# followLineMain.net
KiCad netlist of a schematic drawn in EAGLE
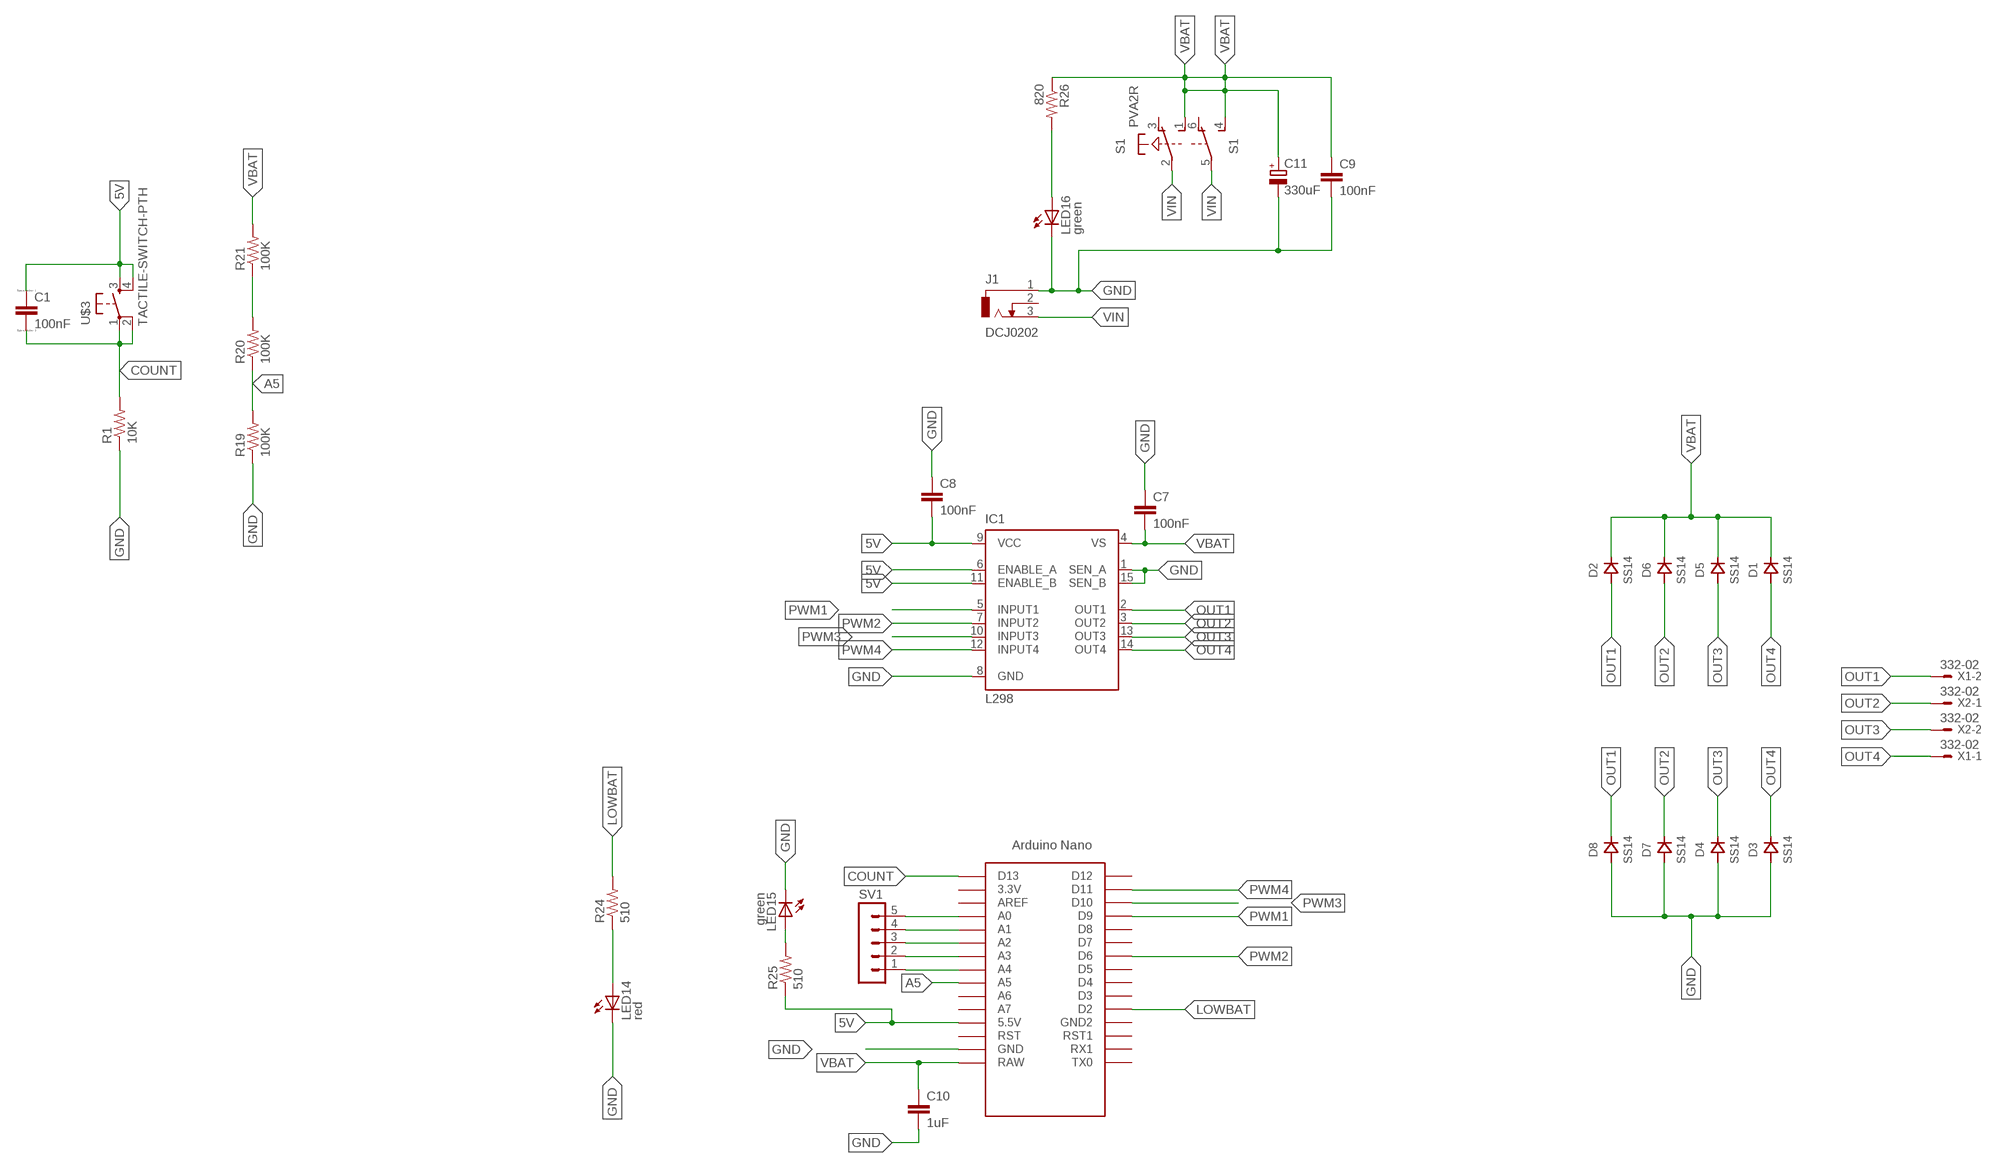
[diagram p0: schematic, sheet 1]

(export (version "E")
  (design (tool "Eeschema 10.0.6"))
  (components
    (comp (ref "C1")
      (value "100nF")
      (footprint "eagle-import:C0603")
      (libsource (lib "eagle-import") (part "CC0603"))
    )
    (comp (ref "C7")
      (value "100nF")
      (footprint "eagle-import:0805")
      (libsource (lib "eagle-import") (part "CAP0805"))
    )
    (comp (ref "C8")
      (value "100nF")
      (footprint "eagle-import:0805")
      (libsource (lib "eagle-import") (part "CAP0805"))
    )
    (comp (ref "C9")
      (value "100nF")
      (footprint "eagle-import:0805")
      (libsource (lib "eagle-import") (part "CAP0805"))
    )
    (comp (ref "C10")
      (value "1uF")
      (footprint "eagle-import:1206")
      (libsource (lib "eagle-import") (part "CAP1206"))
    )
    (comp (ref "C11")
      (value "330uF")
      (footprint "eagle-import:E5-13")
      (libsource (lib "eagle-import") (part "CPOL-EUE5-13"))
    )
    (comp (ref "D1")
      (value "SS14")
      (footprint "eagle-import:DO214")
      (libsource (lib "eagle-import") (part "SS14"))
    )
    (comp (ref "D2")
      (value "SS14")
      (footprint "eagle-import:DO214")
      (libsource (lib "eagle-import") (part "SS14"))
    )
    (comp (ref "D3")
      (value "SS14")
      (footprint "eagle-import:DO214")
      (libsource (lib "eagle-import") (part "SS14"))
    )
    (comp (ref "D4")
      (value "SS14")
      (footprint "eagle-import:DO214")
      (libsource (lib "eagle-import") (part "SS14"))
    )
    (comp (ref "D5")
      (value "SS14")
      (footprint "eagle-import:DO214")
      (libsource (lib "eagle-import") (part "SS14"))
    )
    (comp (ref "D6")
      (value "SS14")
      (footprint "eagle-import:DO214")
      (libsource (lib "eagle-import") (part "SS14"))
    )
    (comp (ref "D7")
      (value "SS14")
      (footprint "eagle-import:DO214")
      (libsource (lib "eagle-import") (part "SS14"))
    )
    (comp (ref "D8")
      (value "SS14")
      (footprint "eagle-import:DO214")
      (libsource (lib "eagle-import") (part "SS14"))
    )
    (comp (ref "IC1")
      (value "L298")
      (footprint "eagle-import:MULTIWATT-15")
      (fields (field (name "MPN") "L298N"))
      (libsource (lib "eagle-import") (part "L298"))
    )
    (comp (ref "J1")
      (value "DCJ0202")
      (footprint "eagle-import:DCJ0202")
      (libsource (lib "eagle-import") (part "DCJ0202"))
    )
    (comp (ref "LED14")
      (value "red")
      (footprint "eagle-import:SML0805")
      (libsource (lib "eagle-import") (part "LEDSML0805"))
    )
    (comp (ref "LED15")
      (value "green")
      (footprint "eagle-import:SML0805")
      (libsource (lib "eagle-import") (part "LEDSML0805"))
    )
    (comp (ref "LED16")
      (value "green")
      (footprint "eagle-import:SML0805")
      (libsource (lib "eagle-import") (part "LEDSML0805"))
    )
    (comp (ref "R1")
      (value "10K")
      (footprint "eagle-import:0805")
      (libsource (lib "eagle-import") (part "RESISTOR0805-RES"))
    )
    (comp (ref "R19")
      (value "100K")
      (footprint "eagle-import:0805")
      (libsource (lib "eagle-import") (part "RESISTOR0805-RES"))
    )
    (comp (ref "R20")
      (value "100K")
      (footprint "eagle-import:0805")
      (libsource (lib "eagle-import") (part "RESISTOR0805-RES"))
    )
    (comp (ref "R21")
      (value "100K")
      (footprint "eagle-import:0805")
      (libsource (lib "eagle-import") (part "RESISTOR0805-RES"))
    )
    (comp (ref "R24")
      (value "510")
      (footprint "eagle-import:0805")
      (libsource (lib "eagle-import") (part "RESISTOR0805-RES"))
    )
    (comp (ref "R25")
      (value "510")
      (footprint "eagle-import:0805")
      (libsource (lib "eagle-import") (part "RESISTOR0805-RES"))
    )
    (comp (ref "R26")
      (value "820")
      (footprint "eagle-import:0805")
      (libsource (lib "eagle-import") (part "RESISTOR0805-RES"))
    )
    (comp (ref "S1")
      (value "PVA2R")
      (footprint "eagle-import:PVA2R")
      (libsource (lib "eagle-import") (part "PVA2R"))
    )
    (comp (ref "SV1")
      (value "MA05-1")
      (footprint "eagle-import:MA05-1")
      (libsource (lib "eagle-import") (part "MA05-1"))
    )
    (comp (ref "U$1")
      (value "NANO")
      (footprint "eagle-import:NANO")
      (libsource (lib "eagle-import") (part "NANO"))
    )
    (comp (ref "U$3")
      (value "TACTILE-SWITCH-PTH")
      (footprint "eagle-import:TAC-SWITCH-PTH")
      (libsource (lib "eagle-import") (part "TACTILE-SWITCH-PTH"))
    )
    (comp (ref "X1")
      (value "332-02")
      (footprint "eagle-import:332-02")
      (libsource (lib "eagle-import") (part "332-02"))
    )
    (comp (ref "X2")
      (value "332-02")
      (footprint "eagle-import:332-02")
      (libsource (lib "eagle-import") (part "332-02"))
    )
  )
  (nets
    (net (code "1") (name "5V") (class "Default")
      (node (ref "C1") (pin "1") (pinfunction "1_1") (pintype "passive"))
      (node (ref "C8") (pin "2") (pinfunction "2_2") (pintype "passive"))
      (node (ref "IC1") (pin "11") (pinfunction "ENABLE_B_11") (pintype "input"))
      (node (ref "IC1") (pin "6") (pinfunction "ENABLE_A_6") (pintype "input"))
      (node (ref "IC1") (pin "9") (pinfunction "VCC_9") (pintype "power_in"))
      (node (ref "R25") (pin "1") (pinfunction "1_1") (pintype "passive"))
      (node (ref "U$1") (pin "5V") (pinfunction "5.5V_5V") (pintype "bidirectional"))
      (node (ref "U$3") (pin "3") (pinfunction "3_3") (pintype "passive"))
      (node (ref "U$3") (pin "4") (pinfunction "4_4") (pintype "passive"))
    )
    (net (code "2") (name "A5") (class "Default")
      (node (ref "R19") (pin "2") (pinfunction "2_2") (pintype "passive"))
      (node (ref "R20") (pin "1") (pinfunction "1_1") (pintype "passive"))
      (node (ref "U$1") (pin "A5") (pinfunction "A5_A5") (pintype "bidirectional"))
    )
    (net (code "3") (name "COUNT") (class "Default")
      (node (ref "C1") (pin "2") (pinfunction "2_2") (pintype "passive"))
      (node (ref "R1") (pin "2") (pinfunction "2_2") (pintype "passive"))
      (node (ref "U$1") (pin "D13") (pinfunction "D13_D13") (pintype "bidirectional"))
      (node (ref "U$3") (pin "1") (pinfunction "1_1") (pintype "passive"))
      (node (ref "U$3") (pin "2") (pinfunction "2_2") (pintype "passive"))
    )
    (net (code "4") (name "GND") (class "Default")
      (node (ref "C10") (pin "2") (pinfunction "2_2") (pintype "passive"))
      (node (ref "C11") (pin "-") (pinfunction "-_-") (pintype "passive"))
      (node (ref "C7") (pin "1") (pinfunction "1_1") (pintype "passive"))
      (node (ref "C8") (pin "1") (pinfunction "1_1") (pintype "passive"))
      (node (ref "C9") (pin "2") (pinfunction "2_2") (pintype "passive"))
      (node (ref "D3") (pin "ANODE") (pinfunction "ANODE_ANODE") (pintype "bidirectional"))
      (node (ref "D4") (pin "ANODE") (pinfunction "ANODE_ANODE") (pintype "bidirectional"))
      (node (ref "D7") (pin "ANODE") (pinfunction "ANODE_ANODE") (pintype "bidirectional"))
      (node (ref "D8") (pin "ANODE") (pinfunction "ANODE_ANODE") (pintype "bidirectional"))
      (node (ref "IC1") (pin "1") (pinfunction "SEN_A_1") (pintype "input"))
      (node (ref "IC1") (pin "15") (pinfunction "SEN_B_15") (pintype "input"))
      (node (ref "IC1") (pin "8") (pinfunction "GND_8") (pintype "power_in"))
      (node (ref "J1") (pin "1") (pinfunction "1_1") (pintype "passive"))
      (node (ref "LED14") (pin "C") (pinfunction "C_C") (pintype "passive"))
      (node (ref "LED15") (pin "C") (pinfunction "C_C") (pintype "passive"))
      (node (ref "LED16") (pin "C") (pinfunction "C_C") (pintype "passive"))
      (node (ref "R1") (pin "1") (pinfunction "1_1") (pintype "passive"))
      (node (ref "R19") (pin "1") (pinfunction "1_1") (pintype "passive"))
      (node (ref "U$1") (pin "GND") (pinfunction "GND_GND") (pintype "bidirectional"))
    )
    (net (code "5") (name "LOWBAT") (class "Default")
      (node (ref "R24") (pin "2") (pinfunction "2_2") (pintype "passive"))
      (node (ref "U$1") (pin "D2") (pinfunction "D2_D2") (pintype "bidirectional"))
    )
    (net (code "6") (name "Net-(LED14-PadA)") (class "Default")
      (node (ref "LED14") (pin "A") (pinfunction "A_A") (pintype "passive"))
      (node (ref "R24") (pin "1") (pinfunction "1_1") (pintype "passive"))
    )
    (net (code "7") (name "Net-(LED15-PadA)") (class "Default")
      (node (ref "LED15") (pin "A") (pinfunction "A_A") (pintype "passive"))
      (node (ref "R25") (pin "2") (pinfunction "2_2") (pintype "passive"))
    )
    (net (code "8") (name "Net-(LED16-PadA)") (class "Default")
      (node (ref "LED16") (pin "A") (pinfunction "A_A") (pintype "passive"))
      (node (ref "R26") (pin "2") (pinfunction "2_2") (pintype "passive"))
    )
    (net (code "9") (name "Net-(R20-Pad2)") (class "Default")
      (node (ref "R20") (pin "2") (pinfunction "2_2") (pintype "passive"))
      (node (ref "R21") (pin "1") (pinfunction "1_1") (pintype "passive"))
    )
    (net (code "10") (name "Net-(SV1-Pad1)") (class "Default")
      (node (ref "SV1") (pin "1") (pinfunction "1_1") (pintype "passive"))
      (node (ref "U$1") (pin "A4") (pinfunction "A4_A4") (pintype "bidirectional"))
    )
    (net (code "11") (name "Net-(SV1-Pad2)") (class "Default")
      (node (ref "SV1") (pin "2") (pinfunction "2_2") (pintype "passive"))
      (node (ref "U$1") (pin "A3") (pinfunction "A3_A3") (pintype "bidirectional"))
    )
    (net (code "12") (name "Net-(SV1-Pad3)") (class "Default")
      (node (ref "SV1") (pin "3") (pinfunction "3_3") (pintype "passive"))
      (node (ref "U$1") (pin "A2") (pinfunction "A2_A2") (pintype "bidirectional"))
    )
    (net (code "13") (name "Net-(SV1-Pad4)") (class "Default")
      (node (ref "SV1") (pin "4") (pinfunction "4_4") (pintype "passive"))
      (node (ref "U$1") (pin "A1") (pinfunction "A1_A1") (pintype "bidirectional"))
    )
    (net (code "14") (name "Net-(SV1-Pad5)") (class "Default")
      (node (ref "SV1") (pin "5") (pinfunction "5_5") (pintype "passive"))
      (node (ref "U$1") (pin "A0") (pinfunction "A0_A0") (pintype "bidirectional"))
    )
    (net (code "15") (name "OUT1") (class "Default")
      (node (ref "D2") (pin "ANODE") (pinfunction "ANODE_ANODE") (pintype "bidirectional"))
      (node (ref "D8") (pin "CATHODE") (pinfunction "CATHODE_CATHODE") (pintype "bidirectional"))
      (node (ref "IC1") (pin "2") (pinfunction "OUT1_2") (pintype "output"))
      (node (ref "X1") (pin "2") (pinfunction "S_2") (pintype "passive"))
    )
    (net (code "16") (name "OUT2") (class "Default")
      (node (ref "D6") (pin "ANODE") (pinfunction "ANODE_ANODE") (pintype "bidirectional"))
      (node (ref "D7") (pin "CATHODE") (pinfunction "CATHODE_CATHODE") (pintype "bidirectional"))
      (node (ref "IC1") (pin "3") (pinfunction "OUT2_3") (pintype "output"))
      (node (ref "X2") (pin "1") (pinfunction "S_1") (pintype "passive"))
    )
    (net (code "17") (name "OUT3") (class "Default")
      (node (ref "D4") (pin "CATHODE") (pinfunction "CATHODE_CATHODE") (pintype "bidirectional"))
      (node (ref "D5") (pin "ANODE") (pinfunction "ANODE_ANODE") (pintype "bidirectional"))
      (node (ref "IC1") (pin "13") (pinfunction "OUT3_13") (pintype "output"))
      (node (ref "X2") (pin "2") (pinfunction "S_2") (pintype "passive"))
    )
    (net (code "18") (name "OUT4") (class "Default")
      (node (ref "D1") (pin "ANODE") (pinfunction "ANODE_ANODE") (pintype "bidirectional"))
      (node (ref "D3") (pin "CATHODE") (pinfunction "CATHODE_CATHODE") (pintype "bidirectional"))
      (node (ref "IC1") (pin "14") (pinfunction "OUT4_14") (pintype "output"))
      (node (ref "X1") (pin "1") (pinfunction "S_1") (pintype "passive"))
    )
    (net (code "19") (name "PWM1") (class "Default")
      (node (ref "IC1") (pin "5") (pinfunction "INPUT1_5") (pintype "input"))
      (node (ref "U$1") (pin "D9") (pinfunction "D9_D9") (pintype "bidirectional"))
    )
    (net (code "20") (name "PWM2") (class "Default")
      (node (ref "IC1") (pin "7") (pinfunction "INPUT2_7") (pintype "input"))
      (node (ref "U$1") (pin "D6") (pinfunction "D6_D6") (pintype "bidirectional"))
    )
    (net (code "21") (name "PWM3") (class "Default")
      (node (ref "IC1") (pin "10") (pinfunction "INPUT3_10") (pintype "input"))
      (node (ref "U$1") (pin "D10") (pinfunction "D10_D10") (pintype "bidirectional"))
    )
    (net (code "22") (name "PWM4") (class "Default")
      (node (ref "IC1") (pin "12") (pinfunction "INPUT4_12") (pintype "input"))
      (node (ref "U$1") (pin "D11") (pinfunction "D11_D11") (pintype "bidirectional"))
    )
    (net (code "23") (name "VBAT") (class "Default")
      (node (ref "C10") (pin "1") (pinfunction "1_1") (pintype "passive"))
      (node (ref "C11") (pin "+") (pinfunction "+_+") (pintype "passive"))
      (node (ref "C7") (pin "2") (pinfunction "2_2") (pintype "passive"))
      (node (ref "C9") (pin "1") (pinfunction "1_1") (pintype "passive"))
      (node (ref "D1") (pin "CATHODE") (pinfunction "CATHODE_CATHODE") (pintype "bidirectional"))
      (node (ref "D2") (pin "CATHODE") (pinfunction "CATHODE_CATHODE") (pintype "bidirectional"))
      (node (ref "D5") (pin "CATHODE") (pinfunction "CATHODE_CATHODE") (pintype "bidirectional"))
      (node (ref "D6") (pin "CATHODE") (pinfunction "CATHODE_CATHODE") (pintype "bidirectional"))
      (node (ref "IC1") (pin "4") (pinfunction "VS_4") (pintype "power_in"))
      (node (ref "R21") (pin "2") (pinfunction "2_2") (pintype "passive"))
      (node (ref "R26") (pin "1") (pinfunction "1_1") (pintype "passive"))
      (node (ref "S1") (pin "1") (pinfunction "S_1") (pintype "passive"))
      (node (ref "S1") (pin "4") (pinfunction "S_4") (pintype "passive"))
      (node (ref "U$1") (pin "RAW") (pinfunction "RAW_RAW") (pintype "bidirectional"))
    )
    (net (code "24") (name "VIN") (class "Default")
      (node (ref "J1") (pin "3") (pinfunction "3_3") (pintype "passive"))
      (node (ref "S1") (pin "2") (pinfunction "P_2") (pintype "passive"))
      (node (ref "S1") (pin "5") (pinfunction "P_5") (pintype "passive"))
    )
    (net (code "25") (name "unconnected-(J1-Pad2)") (class "Default")
      (node (ref "J1") (pin "2") (pinfunction "2_2") (pintype "passive"))
    )
    (net (code "26") (name "unconnected-(S1A-O-Pad3)") (class "Default")
      (node (ref "S1") (pin "3") (pinfunction "O_3") (pintype "passive"))
    )
    (net (code "27") (name "unconnected-(S1B-O-Pad6)") (class "Default")
      (node (ref "S1") (pin "6") (pinfunction "O_6") (pintype "passive"))
    )
    (net (code "28") (name "unconnected-(U$1-GND2-PadGND1)") (class "Default")
      (node (ref "U$1") (pin "GND1") (pinfunction "GND2_GND1") (pintype "bidirectional"))
    )
    (net (code "29") (name "unconnected-(U$1-Pad3.3V)") (class "Default")
      (node (ref "U$1") (pin "3.3V") (pinfunction "3.3V_3.3V") (pintype "bidirectional"))
    )
    (net (code "30") (name "unconnected-(U$1-PadA6)") (class "Default")
      (node (ref "U$1") (pin "A6") (pinfunction "A6_A6") (pintype "bidirectional"))
    )
    (net (code "31") (name "unconnected-(U$1-PadA7)") (class "Default")
      (node (ref "U$1") (pin "A7") (pinfunction "A7_A7") (pintype "bidirectional"))
    )
    (net (code "32") (name "unconnected-(U$1-PadAREF)") (class "Default")
      (node (ref "U$1") (pin "AREF") (pinfunction "AREF_AREF") (pintype "bidirectional"))
    )
    (net (code "33") (name "unconnected-(U$1-PadD3)") (class "Default")
      (node (ref "U$1") (pin "D3") (pinfunction "D3_D3") (pintype "bidirectional"))
    )
    (net (code "34") (name "unconnected-(U$1-PadD4)") (class "Default")
      (node (ref "U$1") (pin "D4") (pinfunction "D4_D4") (pintype "bidirectional"))
    )
    (net (code "35") (name "unconnected-(U$1-PadD5)") (class "Default")
      (node (ref "U$1") (pin "D5") (pinfunction "D5_D5") (pintype "bidirectional"))
    )
    (net (code "36") (name "unconnected-(U$1-PadD7)") (class "Default")
      (node (ref "U$1") (pin "D7") (pinfunction "D7_D7") (pintype "bidirectional"))
    )
    (net (code "37") (name "unconnected-(U$1-PadD8)") (class "Default")
      (node (ref "U$1") (pin "D8") (pinfunction "D8_D8") (pintype "bidirectional"))
    )
    (net (code "38") (name "unconnected-(U$1-PadD12)") (class "Default")
      (node (ref "U$1") (pin "D12") (pinfunction "D12_D12") (pintype "bidirectional"))
    )
    (net (code "39") (name "unconnected-(U$1-PadICSP1)") (class "Default")
      (node (ref "U$1") (pin "ICSP1") (pinfunction "ICSP1_ICSP1") (pintype "bidirectional"))
    )
    (net (code "40") (name "unconnected-(U$1-PadICSP2)") (class "Default")
      (node (ref "U$1") (pin "ICSP2") (pinfunction "ICSP2_ICSP2") (pintype "bidirectional"))
    )
    (net (code "41") (name "unconnected-(U$1-PadICSP3)") (class "Default")
      (node (ref "U$1") (pin "ICSP3") (pinfunction "ICSP3_ICSP3") (pintype "bidirectional"))
    )
    (net (code "42") (name "unconnected-(U$1-PadICSP4)") (class "Default")
      (node (ref "U$1") (pin "ICSP4") (pinfunction "ICSP4_ICSP4") (pintype "bidirectional"))
    )
    (net (code "43") (name "unconnected-(U$1-PadICSP5)") (class "Default")
      (node (ref "U$1") (pin "ICSP5") (pinfunction "ICSP5_ICSP5") (pintype "bidirectional"))
    )
    (net (code "44") (name "unconnected-(U$1-PadICSP6)") (class "Default")
      (node (ref "U$1") (pin "ICSP6") (pinfunction "ICSP6_ICSP6") (pintype "bidirectional"))
    )
    (net (code "45") (name "unconnected-(U$1-PadRST)") (class "Default")
      (node (ref "U$1") (pin "RST") (pinfunction "RST_RST") (pintype "bidirectional"))
    )
    (net (code "46") (name "unconnected-(U$1-PadRST1)") (class "Default")
      (node (ref "U$1") (pin "RST1") (pinfunction "RST1_RST1") (pintype "bidirectional"))
    )
    (net (code "47") (name "unconnected-(U$1-PadRX1)") (class "Default")
      (node (ref "U$1") (pin "RX1") (pinfunction "RX1_RX1") (pintype "bidirectional"))
    )
    (net (code "48") (name "unconnected-(U$1-PadTX0)") (class "Default")
      (node (ref "U$1") (pin "TX0") (pinfunction "TX0_TX0") (pintype "bidirectional"))
    )
  )
)
